# blink1mk3_005t6_5050_4l_usbc.net
KiCad netlist of a schematic drawn in EAGLE
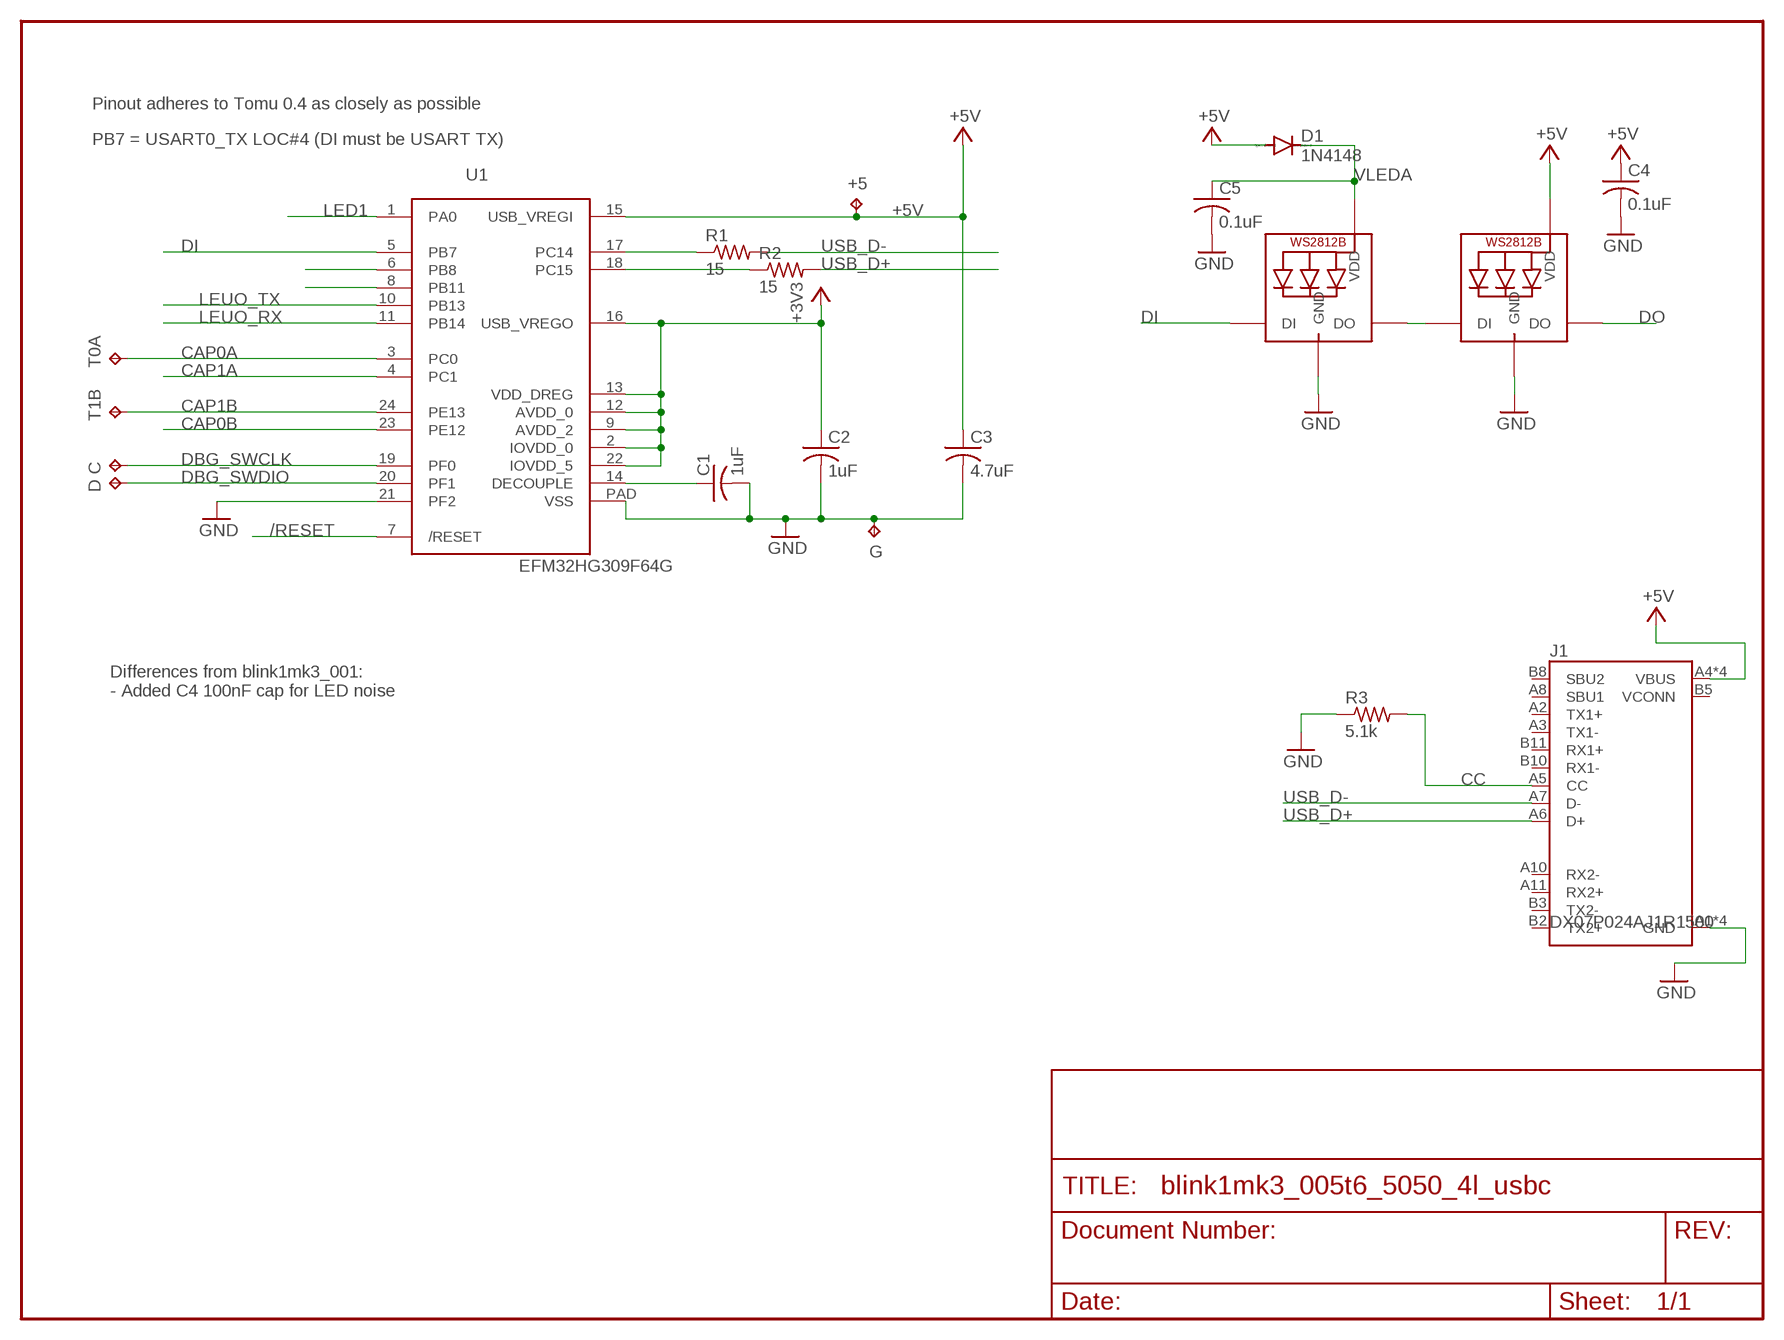
[diagram p0: schematic, sheet 1]

(export (version "E")
  (design (tool "Eeschema 10.0.6"))
  (components
    (comp (ref "+5")
      (value "TPTP10R")
      (footprint "eagle-import:TP10R")
      (libsource (lib "eagle-import") (part "TPTP10R"))
    )
    (comp (ref "C")
      (value "TPTP10R")
      (footprint "eagle-import:TP10R")
      (libsource (lib "eagle-import") (part "TPTP10R"))
    )
    (comp (ref "C1")
      (value "1uF")
      (footprint "eagle-import:C0402")
      (libsource (lib "eagle-import") (part "C-USC0402"))
    )
    (comp (ref "C2")
      (value "1uF")
      (footprint "eagle-import:C0402")
      (libsource (lib "eagle-import") (part "C-USC0402"))
    )
    (comp (ref "C3")
      (value "4.7uF")
      (footprint "eagle-import:C0402")
      (libsource (lib "eagle-import") (part "C-USC0402"))
    )
    (comp (ref "C4")
      (value "0.1uF")
      (footprint "eagle-import:C0402")
      (libsource (lib "eagle-import") (part "C-USC0402"))
    )
    (comp (ref "C5")
      (value "0.1uF")
      (footprint "eagle-import:C0402")
      (libsource (lib "eagle-import") (part "C-USC0402"))
    )
    (comp (ref "D")
      (value "TPTP10R")
      (footprint "eagle-import:TP10R")
      (libsource (lib "eagle-import") (part "TPTP10R"))
    )
    (comp (ref "D1")
      (value "1N4148")
      (footprint "eagle-import:SOD523")
      (libsource (lib "eagle-import") (part "DIODE-SOD523"))
    )
    (comp (ref "G")
      (value "TPTP10R")
      (footprint "eagle-import:TP10R")
      (libsource (lib "eagle-import") (part "TPTP10R"))
    )
    (comp (ref "J1")
      (value "DX07P024AJ1R1500")
      (footprint "eagle-import:JAE_DX07P024AJ1R1500")
      (fields (field (name "DIGI-KEY_PART_NUMBER") "670-2868-1-ND") (field (name "MF") "JAE Electronics"))
      (libsource (lib "eagle-import") (part "DX07P024AJ1R1500"))
    )
    (comp (ref "LED1")
      (value "SK6812MINI")
      (footprint "eagle-import:LED3535")
      (libsource (lib "eagle-import") (part "WS2812B3535"))
    )
    (comp (ref "LED2")
      (value "SK6812MINI")
      (footprint "eagle-import:LED3535")
      (libsource (lib "eagle-import") (part "WS2812B3535"))
    )
    (comp (ref "R1")
      (value "15")
      (footprint "eagle-import:R0402")
      (libsource (lib "eagle-import") (part "rcl_334_R-US_R0402"))
    )
    (comp (ref "R2")
      (value "15")
      (footprint "eagle-import:R0402")
      (libsource (lib "eagle-import") (part "rcl_334_R-US_R0402"))
    )
    (comp (ref "R3")
      (value "5.1k")
      (footprint "eagle-import:R0402")
      (libsource (lib "eagle-import") (part "R-US_R0402"))
    )
    (comp (ref "T0A")
      (value "TPTP15R")
      (footprint "eagle-import:TP15R")
      (libsource (lib "eagle-import") (part "TPTP15R"))
    )
    (comp (ref "T1B")
      (value "TPTP15R")
      (footprint "eagle-import:TP15R")
      (libsource (lib "eagle-import") (part "TPTP15R"))
    )
    (comp (ref "U1")
      (value "EFM32HG309F64G")
      (footprint "eagle-import:QFN24PAD")
      (libsource (lib "eagle-import") (part "EFM32HG309F64G"))
    )
  )
  (nets
    (net (code "1") (name "+3V3") (class "Default")
      (node (ref "C2") (pin "1") (pinfunction "1_1") (pintype "passive"))
      (node (ref "U1") (pin "12") (pinfunction "AVDD_0_12") (pintype "bidirectional"))
      (node (ref "U1") (pin "13") (pinfunction "VDD_DREG_13") (pintype "bidirectional"))
      (node (ref "U1") (pin "16") (pinfunction "USB_VREGO_16") (pintype "bidirectional"))
      (node (ref "U1") (pin "2") (pinfunction "IOVDD_0_2") (pintype "bidirectional"))
      (node (ref "U1") (pin "22") (pinfunction "IOVDD_5_22") (pintype "bidirectional"))
      (node (ref "U1") (pin "9") (pinfunction "AVDD_2_9") (pintype "bidirectional"))
    )
    (net (code "2") (name "+5V") (class "Default")
      (node (ref "+5") (pin "TP") (pinfunction "TP_TP") (pintype "input"))
      (node (ref "C3") (pin "1") (pinfunction "1_1") (pintype "passive"))
      (node (ref "C4") (pin "1") (pinfunction "1_1") (pintype "passive"))
      (node (ref "D1") (pin "A") (pinfunction "A_A") (pintype "passive"))
      (node (ref "J1") (pin "A4") (pinfunction "VBUS_A4") (pintype "power_in"))
      (node (ref "J1") (pin "A9") (pinfunction "VBUS_A9") (pintype "power_in"))
      (node (ref "J1") (pin "B4") (pinfunction "VBUS_B4") (pintype "power_in"))
      (node (ref "J1") (pin "B9") (pinfunction "VBUS_B9") (pintype "power_in"))
      (node (ref "LED2") (pin "2") (pinfunction "VDD_2") (pintype "power_in"))
      (node (ref "U1") (pin "15") (pinfunction "USB_VREGI_15") (pintype "bidirectional"))
    )
    (net (code "3") (name "/CAP0A") (class "Default")
      (node (ref "T0A") (pin "TP") (pinfunction "TP_TP") (pintype "input"))
      (node (ref "U1") (pin "3") (pinfunction "PC0_3") (pintype "bidirectional"))
    )
    (net (code "4") (name "/CAP0B") (class "Default")
      (node (ref "U1") (pin "23") (pinfunction "PE12_23") (pintype "bidirectional"))
    )
    (net (code "5") (name "/CAP1A") (class "Default")
      (node (ref "U1") (pin "4") (pinfunction "PC1_4") (pintype "bidirectional"))
    )
    (net (code "6") (name "/CAP1B") (class "Default")
      (node (ref "T1B") (pin "TP") (pinfunction "TP_TP") (pintype "input"))
      (node (ref "U1") (pin "24") (pinfunction "PE13_24") (pintype "bidirectional"))
    )
    (net (code "7") (name "/CC") (class "Default")
      (node (ref "J1") (pin "A5") (pinfunction "CC_A5") (pintype "bidirectional"))
      (node (ref "R3") (pin "2") (pinfunction "2_2") (pintype "passive"))
    )
    (net (code "8") (name "/DBG_SWCLK") (class "Default")
      (node (ref "C") (pin "TP") (pinfunction "TP_TP") (pintype "input"))
      (node (ref "U1") (pin "19") (pinfunction "PF0_19") (pintype "bidirectional"))
    )
    (net (code "9") (name "/DBG_SWDIO") (class "Default")
      (node (ref "D") (pin "TP") (pinfunction "TP_TP") (pintype "input"))
      (node (ref "U1") (pin "20") (pinfunction "PF1_20") (pintype "bidirectional"))
    )
    (net (code "10") (name "/DI") (class "Default")
      (node (ref "LED1") (pin "1") (pinfunction "DI_1") (pintype "input"))
      (node (ref "U1") (pin "5") (pinfunction "PB7_5") (pintype "bidirectional"))
    )
    (net (code "11") (name "/DO") (class "Default")
      (node (ref "LED2") (pin "3") (pinfunction "DO_3") (pintype "output"))
    )
    (net (code "12") (name "/LED1") (class "Default")
      (node (ref "U1") (pin "1") (pinfunction "PA0_1") (pintype "bidirectional"))
    )
    (net (code "13") (name "/LEUO_RX") (class "Default")
      (node (ref "U1") (pin "11") (pinfunction "PB14_11") (pintype "bidirectional"))
    )
    (net (code "14") (name "/LEUO_TX") (class "Default")
      (node (ref "U1") (pin "10") (pinfunction "PB13_10") (pintype "bidirectional"))
    )
    (net (code "15") (name "/USB_D+") (class "Default")
      (node (ref "J1") (pin "A6") (pinfunction "D+_A6") (pintype "bidirectional"))
      (node (ref "R2") (pin "2") (pinfunction "2_2") (pintype "passive"))
    )
    (net (code "16") (name "/USB_D-") (class "Default")
      (node (ref "J1") (pin "A7") (pinfunction "D-_A7") (pintype "bidirectional"))
      (node (ref "R1") (pin "2") (pinfunction "2_2") (pintype "passive"))
    )
    (net (code "17") (name "/VCONN") (class "Default")
      (node (ref "J1") (pin "B5") (pinfunction "VCONN_B5") (pintype "power_in"))
    )
    (net (code "18") (name "/VLEDA") (class "Default")
      (node (ref "C5") (pin "1") (pinfunction "1_1") (pintype "passive"))
      (node (ref "D1") (pin "C") (pinfunction "C_C") (pintype "passive"))
      (node (ref "LED1") (pin "2") (pinfunction "VDD_2") (pintype "power_in"))
    )
    (net (code "19") (name "/{slash}RESET") (class "Default")
      (node (ref "U1") (pin "7") (pinfunction "/RESET_7") (pintype "bidirectional"))
    )
    (net (code "20") (name "GND") (class "Default")
      (node (ref "C1") (pin "2") (pinfunction "2_2") (pintype "passive"))
      (node (ref "C2") (pin "2") (pinfunction "2_2") (pintype "passive"))
      (node (ref "C3") (pin "2") (pinfunction "2_2") (pintype "passive"))
      (node (ref "C4") (pin "2") (pinfunction "2_2") (pintype "passive"))
      (node (ref "C5") (pin "2") (pinfunction "2_2") (pintype "passive"))
      (node (ref "G") (pin "TP") (pinfunction "TP_TP") (pintype "input"))
      (node (ref "J1") (pin "A1") (pinfunction "GND_A1") (pintype "power_in"))
      (node (ref "J1") (pin "A12") (pinfunction "GND_A12") (pintype "power_in"))
      (node (ref "J1") (pin "B1") (pinfunction "GND_B1") (pintype "power_in"))
      (node (ref "J1") (pin "B12") (pinfunction "GND_B12") (pintype "power_in"))
      (node (ref "LED1") (pin "4") (pinfunction "GND_4") (pintype "power_in"))
      (node (ref "LED2") (pin "4") (pinfunction "GND_4") (pintype "power_in"))
      (node (ref "R3") (pin "1") (pinfunction "1_1") (pintype "passive"))
      (node (ref "U1") (pin "21") (pinfunction "PF2_21") (pintype "bidirectional"))
      (node (ref "U1") (pin "PAD") (pinfunction "VSS_PAD") (pintype "bidirectional"))
    )
    (net (code "21") (name "Net-(LED1-DO)") (class "Default")
      (node (ref "LED1") (pin "3") (pinfunction "DO_3") (pintype "output"))
      (node (ref "LED2") (pin "1") (pinfunction "DI_1") (pintype "input"))
    )
    (net (code "22") (name "Net-(U1-DECOUPLE)") (class "Default")
      (node (ref "C1") (pin "1") (pinfunction "1_1") (pintype "passive"))
      (node (ref "U1") (pin "14") (pinfunction "DECOUPLE_14") (pintype "bidirectional"))
    )
    (net (code "23") (name "Net-(U1-PC14)") (class "Default")
      (node (ref "R1") (pin "1") (pinfunction "1_1") (pintype "passive"))
      (node (ref "U1") (pin "17") (pinfunction "PC14_17") (pintype "bidirectional"))
    )
    (net (code "24") (name "Net-(U1-PC15)") (class "Default")
      (node (ref "R2") (pin "1") (pinfunction "1_1") (pintype "passive"))
      (node (ref "U1") (pin "18") (pinfunction "PC15_18") (pintype "bidirectional"))
    )
    (net (code "25") (name "unconnected-(J1-RX1+-PadB11)") (class "Default")
      (node (ref "J1") (pin "B11") (pinfunction "RX1+_B11") (pintype "bidirectional"))
    )
    (net (code "26") (name "unconnected-(J1-RX1--PadB10)") (class "Default")
      (node (ref "J1") (pin "B10") (pinfunction "RX1-_B10") (pintype "bidirectional"))
    )
    (net (code "27") (name "unconnected-(J1-RX2+-PadA11)") (class "Default")
      (node (ref "J1") (pin "A11") (pinfunction "RX2+_A11") (pintype "bidirectional"))
    )
    (net (code "28") (name "unconnected-(J1-RX2--PadA10)") (class "Default")
      (node (ref "J1") (pin "A10") (pinfunction "RX2-_A10") (pintype "bidirectional"))
    )
    (net (code "29") (name "unconnected-(J1-SBU1-PadA8)") (class "Default")
      (node (ref "J1") (pin "A8") (pinfunction "SBU1_A8") (pintype "bidirectional"))
    )
    (net (code "30") (name "unconnected-(J1-SBU2-PadB8)") (class "Default")
      (node (ref "J1") (pin "B8") (pinfunction "SBU2_B8") (pintype "bidirectional"))
    )
    (net (code "31") (name "unconnected-(J1-TX1+-PadA2)") (class "Default")
      (node (ref "J1") (pin "A2") (pinfunction "TX1+_A2") (pintype "bidirectional"))
    )
    (net (code "32") (name "unconnected-(J1-TX1--PadA3)") (class "Default")
      (node (ref "J1") (pin "A3") (pinfunction "TX1-_A3") (pintype "bidirectional"))
    )
    (net (code "33") (name "unconnected-(J1-TX2+-PadB2)") (class "Default")
      (node (ref "J1") (pin "B2") (pinfunction "TX2+_B2") (pintype "bidirectional"))
    )
    (net (code "34") (name "unconnected-(J1-TX2--PadB3)") (class "Default")
      (node (ref "J1") (pin "B3") (pinfunction "TX2-_B3") (pintype "bidirectional"))
    )
    (net (code "35") (name "unconnected-(U1-PB8-Pad6)") (class "Default")
      (node (ref "U1") (pin "6") (pinfunction "PB8_6") (pintype "bidirectional"))
    )
    (net (code "36") (name "unconnected-(U1-PB11-Pad8)") (class "Default")
      (node (ref "U1") (pin "8") (pinfunction "PB11_8") (pintype "bidirectional"))
    )
  )
)
